# motor_shield_A.net
KiCad netlist of a schematic drawn in EAGLE
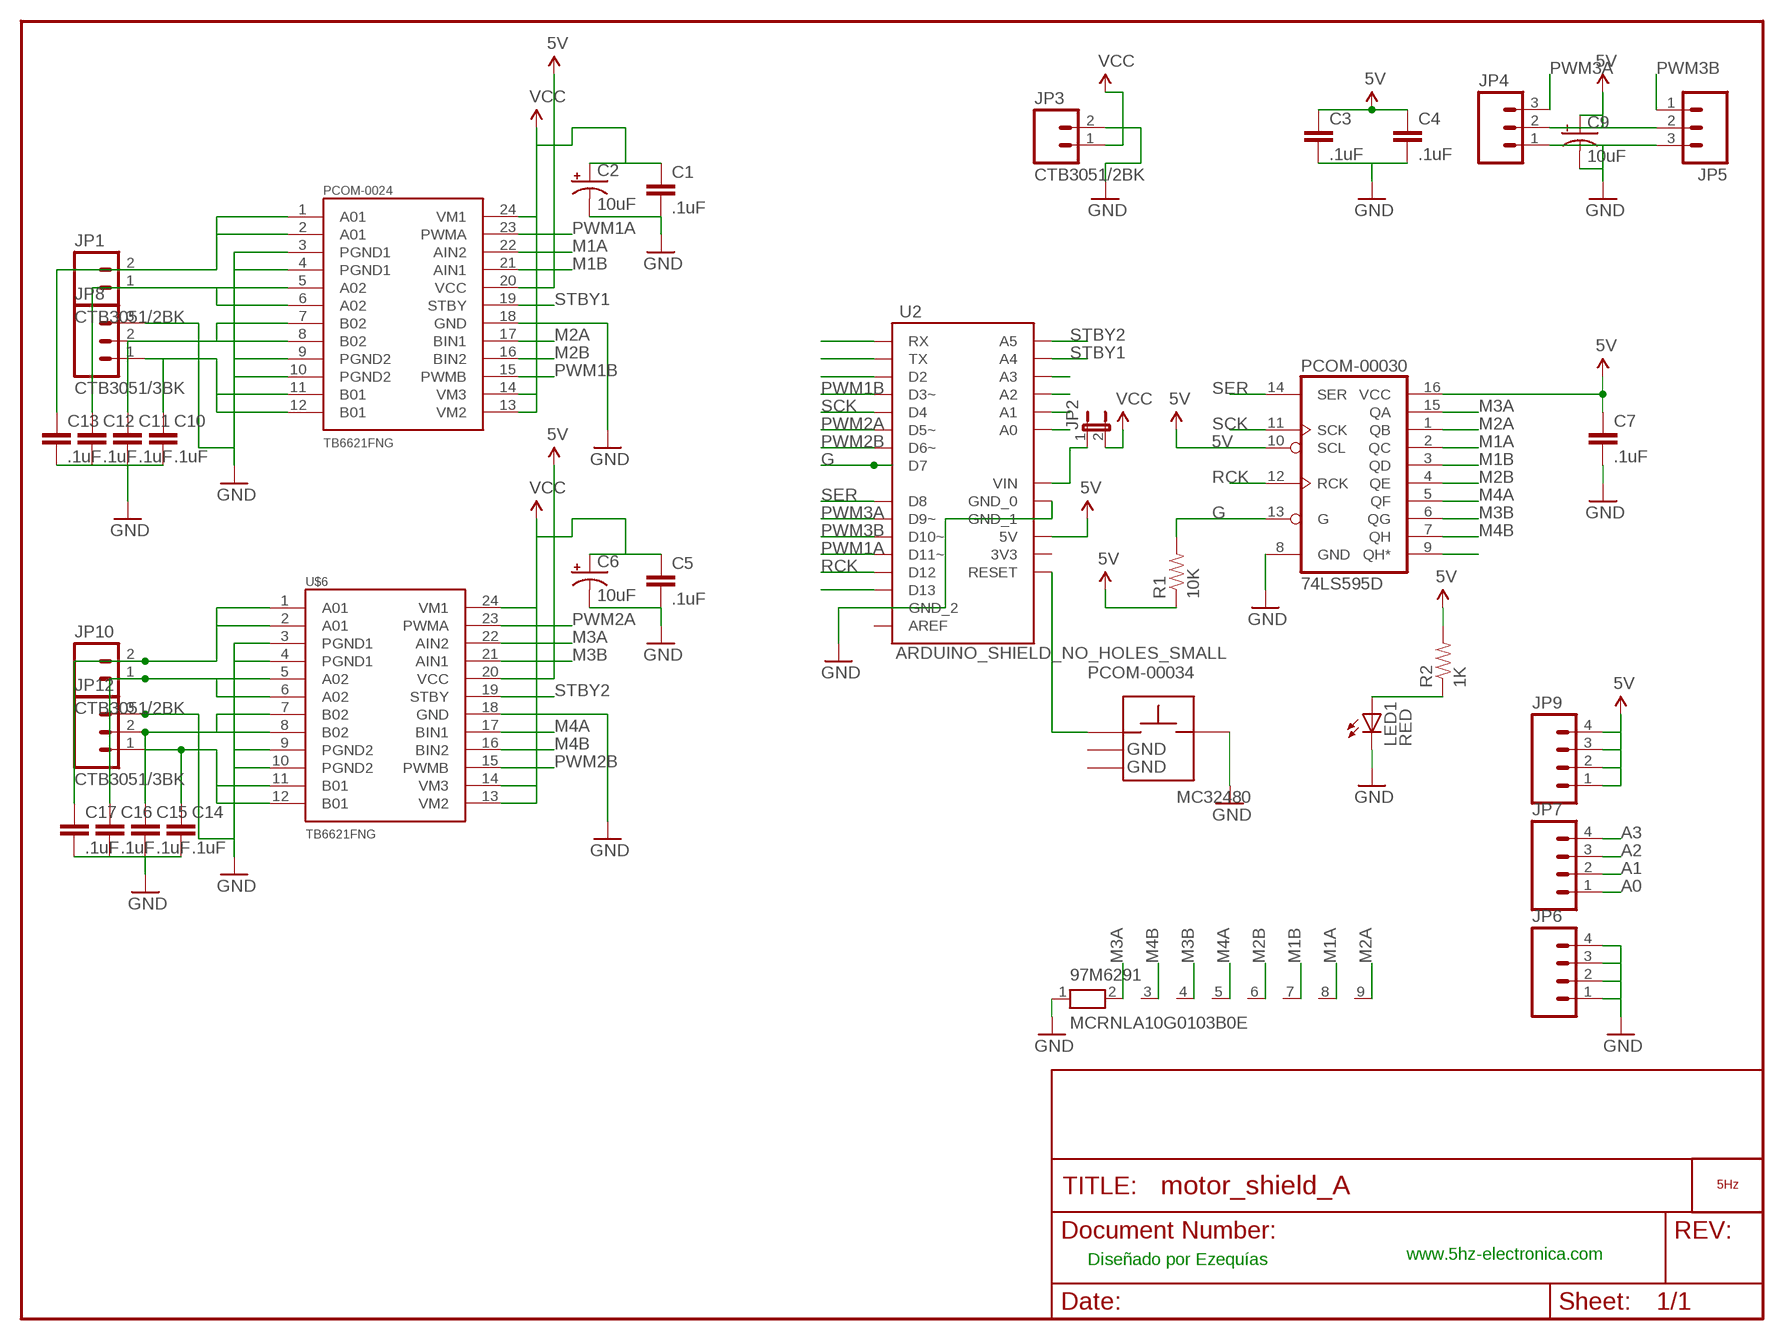
[diagram p0: schematic, sheet 1]

(export (version "E")
  (design (tool "Eeschema 10.0.6"))
  (components
    (comp (ref "97M6291")
      (value "MCRNLA10G0103B0E")
      (footprint "eagle-import:RN-9")
      (libsource (lib "eagle-import") (part "RN08"))
    )
    (comp (ref "C1")
      (value ".1uF")
      (footprint "eagle-import:0603-CAP")
      (libsource (lib "eagle-import") (part "CAP0603-CAP"))
    )
    (comp (ref "C2")
      (value "10uF")
      (footprint "eagle-import:EIA3528-KIT")
      (libsource (lib "eagle-import") (part "CAP_POL3528-KIT"))
    )
    (comp (ref "C3")
      (value ".1uF")
      (footprint "eagle-import:0603-CAP")
      (libsource (lib "eagle-import") (part "CAP0603-CAP"))
    )
    (comp (ref "C4")
      (value ".1uF")
      (footprint "eagle-import:0603-CAP")
      (libsource (lib "eagle-import") (part "CAP0603-CAP"))
    )
    (comp (ref "C5")
      (value ".1uF")
      (footprint "eagle-import:0603-CAP")
      (libsource (lib "eagle-import") (part "CAP0603-CAP"))
    )
    (comp (ref "C6")
      (value "10uF")
      (footprint "eagle-import:EIA3528-KIT")
      (libsource (lib "eagle-import") (part "CAP_POL3528-KIT"))
    )
    (comp (ref "C7")
      (value ".1uF")
      (footprint "eagle-import:0603-CAP")
      (libsource (lib "eagle-import") (part "CAP0603-CAP"))
    )
    (comp (ref "C9")
      (value "10uF")
      (footprint "eagle-import:EIA3216")
      (libsource (lib "eagle-import") (part "CAP_POL1206"))
    )
    (comp (ref "C10")
      (value ".1uF")
      (footprint "eagle-import:0603-CAP")
      (libsource (lib "eagle-import") (part "CAP0603-CAP"))
    )
    (comp (ref "C11")
      (value ".1uF")
      (footprint "eagle-import:0603-CAP")
      (libsource (lib "eagle-import") (part "CAP0603-CAP"))
    )
    (comp (ref "C12")
      (value ".1uF")
      (footprint "eagle-import:0603-CAP")
      (libsource (lib "eagle-import") (part "CAP0603-CAP"))
    )
    (comp (ref "C13")
      (value ".1uF")
      (footprint "eagle-import:0603-CAP")
      (libsource (lib "eagle-import") (part "CAP0603-CAP"))
    )
    (comp (ref "C14")
      (value ".1uF")
      (footprint "eagle-import:0603-CAP")
      (libsource (lib "eagle-import") (part "CAP0603-CAP"))
    )
    (comp (ref "C15")
      (value ".1uF")
      (footprint "eagle-import:0603-CAP")
      (libsource (lib "eagle-import") (part "CAP0603-CAP"))
    )
    (comp (ref "C16")
      (value ".1uF")
      (footprint "eagle-import:0603-CAP")
      (libsource (lib "eagle-import") (part "CAP0603-CAP"))
    )
    (comp (ref "C17")
      (value ".1uF")
      (footprint "eagle-import:0603-CAP")
      (libsource (lib "eagle-import") (part "CAP0603-CAP"))
    )
    (comp (ref "JP1")
      (value "CTB3051/2BK")
      (footprint "eagle-import:SCREWTERMINAL-3.5MM-2")
      (libsource (lib "eagle-import") (part "M023.5MM"))
    )
    (comp (ref "JP2")
      (value "JUMPER-2PTH")
      (footprint "eagle-import:1X02")
      (libsource (lib "eagle-import") (part "JUMPER-2PTH"))
    )
    (comp (ref "JP3")
      (value "CTB3051/2BK")
      (footprint "eagle-import:SCREWTERMINAL-3.5MM-2")
      (libsource (lib "eagle-import") (part "M023.5MM"))
    )
    (comp (ref "JP4")
      (value "M03PTH")
      (footprint "eagle-import:1X03")
      (libsource (lib "eagle-import") (part "SparkFun_old_M03PTH"))
    )
    (comp (ref "JP5")
      (value "M03PTH")
      (footprint "eagle-import:1X03")
      (libsource (lib "eagle-import") (part "SparkFun_old_M03PTH"))
    )
    (comp (ref "JP6")
      (value "M04PTH")
      (footprint "eagle-import:1X04")
      (libsource (lib "eagle-import") (part "M04PTH"))
    )
    (comp (ref "JP7")
      (value "M04PTH")
      (footprint "eagle-import:1X04")
      (libsource (lib "eagle-import") (part "M04PTH"))
    )
    (comp (ref "JP8")
      (value "CTB3051/3BK")
      (footprint "eagle-import:SCREWTERMINAL-3.5MM-3")
      (libsource (lib "eagle-import") (part "M03SCREW"))
    )
    (comp (ref "JP9")
      (value "M04PTH")
      (footprint "eagle-import:1X04")
      (libsource (lib "eagle-import") (part "M04PTH"))
    )
    (comp (ref "JP10")
      (value "CTB3051/2BK")
      (footprint "eagle-import:SCREWTERMINAL-3.5MM-2")
      (libsource (lib "eagle-import") (part "M023.5MM"))
    )
    (comp (ref "JP12")
      (value "CTB3051/3BK")
      (footprint "eagle-import:SCREWTERMINAL-3.5MM-3")
      (libsource (lib "eagle-import") (part "M03SCREW"))
    )
    (comp (ref "LED1")
      (value "RED")
      (footprint "eagle-import:LED-0603")
      (libsource (lib "eagle-import") (part "LED0603"))
    )
    (comp (ref "LOGO1")
      (value "LOGO_5HZ_H_COOPER_10MM")
      (footprint "eagle-import:5HZ_LOGO_H_COOPER_10MM")
      (libsource (lib "eagle-import") (part "LOGO_5HZ_H_COOPER_10MM"))
    )
    (comp (ref "PCOM-0024")
      (value "TB6621FNG")
      (footprint "eagle-import:SSOP24")
      (libsource (lib "eagle-import") (part "TB6621FNG"))
    )
    (comp (ref "PCOM-00030")
      (value "74LS595D")
      (footprint "eagle-import:SO16")
      (libsource (lib "eagle-import") (part "74595DLS"))
    )
    (comp (ref "PCOM-00034")
      (value "MC32480")
      (footprint "eagle-import:MC32840")
      (libsource (lib "eagle-import") (part "TACTILE_SWITCH_MC32480"))
    )
    (comp (ref "R1")
      (value "10K")
      (footprint "eagle-import:0603-RES")
      (libsource (lib "eagle-import") (part "RESISTOR0603-RES"))
    )
    (comp (ref "R2")
      (value "1K")
      (footprint "eagle-import:0603-RES")
      (libsource (lib "eagle-import") (part "RESISTOR0603-RES"))
    )
    (comp (ref "U$6")
      (value "TB6621FNG")
      (footprint "eagle-import:SSOP24")
      (libsource (lib "eagle-import") (part "TB6621FNG"))
    )
    (comp (ref "U2")
      (value "ARDUINO_SHIELD_NO_HOLES_SMALL")
      (footprint "eagle-import:UNO_SHIELD_SMALL_NO_HOLES")
      (libsource (lib "eagle-import") (part "ARDUINO_SHIELD_NO_HOLES_SMALL"))
    )
  )
  (nets
    (net (code "1") (name "/A0") (class "Default")
      (node (ref "JP7") (pin "1") (pinfunction "1_1") (pintype "passive"))
      (node (ref "U2") (pin "A0") (pinfunction "A0_A0") (pintype "bidirectional"))
    )
    (net (code "2") (name "/A1") (class "Default")
      (node (ref "JP7") (pin "2") (pinfunction "2_2") (pintype "passive"))
      (node (ref "U2") (pin "A1") (pinfunction "A1_A1") (pintype "bidirectional"))
    )
    (net (code "3") (name "/A2") (class "Default")
      (node (ref "JP7") (pin "3") (pinfunction "3_3") (pintype "passive"))
      (node (ref "U2") (pin "A2") (pinfunction "A2_A2") (pintype "bidirectional"))
    )
    (net (code "4") (name "/A3") (class "Default")
      (node (ref "JP7") (pin "4") (pinfunction "4_4") (pintype "passive"))
      (node (ref "U2") (pin "A3") (pinfunction "A3_A3") (pintype "bidirectional"))
    )
    (net (code "5") (name "/G") (class "Default")
      (node (ref "PCOM-00030") (pin "13") (pinfunction "G_13") (pintype "input"))
      (node (ref "R1") (pin "2") (pinfunction "2_2") (pintype "passive"))
      (node (ref "U2") (pin "D7") (pinfunction "D7_D7") (pintype "bidirectional"))
    )
    (net (code "6") (name "/M1A") (class "Default")
      (node (ref "97M6291") (pin "8") (pinfunction "8_8") (pintype "passive"))
      (node (ref "PCOM-00030") (pin "2") (pinfunction "QC_2") (pintype "tri_state"))
      (node (ref "PCOM-0024") (pin "22") (pinfunction "AIN2_22") (pintype "bidirectional"))
    )
    (net (code "7") (name "/M1B") (class "Default")
      (node (ref "97M6291") (pin "7") (pinfunction "7_7") (pintype "passive"))
      (node (ref "PCOM-00030") (pin "3") (pinfunction "QD_3") (pintype "tri_state"))
      (node (ref "PCOM-0024") (pin "21") (pinfunction "AIN1_21") (pintype "bidirectional"))
    )
    (net (code "8") (name "/M2A") (class "Default")
      (node (ref "97M6291") (pin "9") (pinfunction "9_9") (pintype "passive"))
      (node (ref "PCOM-00030") (pin "1") (pinfunction "QB_1") (pintype "tri_state"))
      (node (ref "PCOM-0024") (pin "17") (pinfunction "BIN1_17") (pintype "bidirectional"))
    )
    (net (code "9") (name "/M2B") (class "Default")
      (node (ref "97M6291") (pin "6") (pinfunction "6_6") (pintype "passive"))
      (node (ref "PCOM-00030") (pin "4") (pinfunction "QE_4") (pintype "tri_state"))
      (node (ref "PCOM-0024") (pin "16") (pinfunction "BIN2_16") (pintype "bidirectional"))
    )
    (net (code "10") (name "/M3A") (class "Default")
      (node (ref "97M6291") (pin "2") (pinfunction "2_2") (pintype "passive"))
      (node (ref "PCOM-00030") (pin "15") (pinfunction "QA_15") (pintype "tri_state"))
      (node (ref "U$6") (pin "22") (pinfunction "AIN2_22") (pintype "bidirectional"))
    )
    (net (code "11") (name "/M3B") (class "Default")
      (node (ref "97M6291") (pin "4") (pinfunction "4_4") (pintype "passive"))
      (node (ref "PCOM-00030") (pin "6") (pinfunction "QG_6") (pintype "tri_state"))
      (node (ref "U$6") (pin "21") (pinfunction "AIN1_21") (pintype "bidirectional"))
    )
    (net (code "12") (name "/M4A") (class "Default")
      (node (ref "97M6291") (pin "5") (pinfunction "5_5") (pintype "passive"))
      (node (ref "PCOM-00030") (pin "5") (pinfunction "QF_5") (pintype "tri_state"))
      (node (ref "U$6") (pin "17") (pinfunction "BIN1_17") (pintype "bidirectional"))
    )
    (net (code "13") (name "/M4B") (class "Default")
      (node (ref "97M6291") (pin "3") (pinfunction "3_3") (pintype "passive"))
      (node (ref "PCOM-00030") (pin "7") (pinfunction "QH_7") (pintype "tri_state"))
      (node (ref "U$6") (pin "16") (pinfunction "BIN2_16") (pintype "bidirectional"))
    )
    (net (code "14") (name "/PWM1A") (class "Default")
      (node (ref "PCOM-0024") (pin "23") (pinfunction "PWMA_23") (pintype "bidirectional"))
      (node (ref "U2") (pin "D11") (pinfunction "D11~{}_D11") (pintype "bidirectional"))
    )
    (net (code "15") (name "/PWM1B") (class "Default")
      (node (ref "PCOM-0024") (pin "15") (pinfunction "PWMB_15") (pintype "bidirectional"))
      (node (ref "U2") (pin "D3") (pinfunction "D3~{}_D3") (pintype "bidirectional"))
    )
    (net (code "16") (name "/PWM2A") (class "Default")
      (node (ref "U$6") (pin "23") (pinfunction "PWMA_23") (pintype "bidirectional"))
      (node (ref "U2") (pin "D5") (pinfunction "D5~{}_D5") (pintype "bidirectional"))
    )
    (net (code "17") (name "/PWM2B") (class "Default")
      (node (ref "U$6") (pin "15") (pinfunction "PWMB_15") (pintype "bidirectional"))
      (node (ref "U2") (pin "D6") (pinfunction "D6~{}_D6") (pintype "bidirectional"))
    )
    (net (code "18") (name "/PWM3A") (class "Default")
      (node (ref "JP4") (pin "3") (pinfunction "3_3") (pintype "passive"))
      (node (ref "U2") (pin "D9") (pinfunction "D9~{}_D9") (pintype "bidirectional"))
    )
    (net (code "19") (name "/PWM3B") (class "Default")
      (node (ref "JP5") (pin "1") (pinfunction "1_1") (pintype "passive"))
      (node (ref "U2") (pin "D10") (pinfunction "D10~{}_D10") (pintype "bidirectional"))
    )
    (net (code "20") (name "/RCK") (class "Default")
      (node (ref "PCOM-00030") (pin "12") (pinfunction "RCK_12") (pintype "input"))
      (node (ref "U2") (pin "D12") (pinfunction "D12_D12") (pintype "bidirectional"))
    )
    (net (code "21") (name "/SCK") (class "Default")
      (node (ref "PCOM-00030") (pin "11") (pinfunction "SCK_11") (pintype "input"))
      (node (ref "U2") (pin "D4") (pinfunction "D4_D4") (pintype "bidirectional"))
    )
    (net (code "22") (name "/SER") (class "Default")
      (node (ref "PCOM-00030") (pin "14") (pinfunction "SER_14") (pintype "input"))
      (node (ref "U2") (pin "D8") (pinfunction "D8_D8") (pintype "bidirectional"))
    )
    (net (code "23") (name "/STBY1") (class "Default")
      (node (ref "PCOM-0024") (pin "19") (pinfunction "STBY_19") (pintype "bidirectional"))
      (node (ref "U2") (pin "A4") (pinfunction "A4_A4") (pintype "bidirectional"))
    )
    (net (code "24") (name "/STBY2") (class "Default")
      (node (ref "U$6") (pin "19") (pinfunction "STBY_19") (pintype "bidirectional"))
      (node (ref "U2") (pin "A5") (pinfunction "A5_A5") (pintype "bidirectional"))
    )
    (net (code "25") (name "5V") (class "Default")
      (node (ref "C3") (pin "1") (pinfunction "1_1") (pintype "passive"))
      (node (ref "C4") (pin "1") (pinfunction "1_1") (pintype "passive"))
      (node (ref "C7") (pin "1") (pinfunction "1_1") (pintype "passive"))
      (node (ref "C9") (pin "A") (pinfunction "+_A") (pintype "passive"))
      (node (ref "JP4") (pin "2") (pinfunction "2_2") (pintype "passive"))
      (node (ref "JP5") (pin "2") (pinfunction "2_2") (pintype "passive"))
      (node (ref "JP9") (pin "1") (pinfunction "1_1") (pintype "passive"))
      (node (ref "JP9") (pin "2") (pinfunction "2_2") (pintype "passive"))
      (node (ref "JP9") (pin "3") (pinfunction "3_3") (pintype "passive"))
      (node (ref "JP9") (pin "4") (pinfunction "4_4") (pintype "passive"))
      (node (ref "PCOM-00030") (pin "10") (pinfunction "SCL_10") (pintype "input"))
      (node (ref "PCOM-00030") (pin "16") (pinfunction "VCC_16") (pintype "power_in"))
      (node (ref "PCOM-0024") (pin "20") (pinfunction "VCC_20") (pintype "bidirectional"))
      (node (ref "R1") (pin "1") (pinfunction "1_1") (pintype "passive"))
      (node (ref "R2") (pin "2") (pinfunction "2_2") (pintype "passive"))
      (node (ref "U$6") (pin "20") (pinfunction "VCC_20") (pintype "bidirectional"))
      (node (ref "U2") (pin "5V") (pinfunction "5V_5V") (pintype "bidirectional"))
    )
    (net (code "26") (name "GND") (class "Default")
      (node (ref "97M6291") (pin "1") (pinfunction "1_1") (pintype "passive"))
      (node (ref "C1") (pin "2") (pinfunction "2_2") (pintype "passive"))
      (node (ref "C10") (pin "2") (pinfunction "2_2") (pintype "passive"))
      (node (ref "C11") (pin "2") (pinfunction "2_2") (pintype "passive"))
      (node (ref "C12") (pin "2") (pinfunction "2_2") (pintype "passive"))
      (node (ref "C13") (pin "2") (pinfunction "2_2") (pintype "passive"))
      (node (ref "C14") (pin "2") (pinfunction "2_2") (pintype "passive"))
      (node (ref "C15") (pin "2") (pinfunction "2_2") (pintype "passive"))
      (node (ref "C16") (pin "2") (pinfunction "2_2") (pintype "passive"))
      (node (ref "C17") (pin "2") (pinfunction "2_2") (pintype "passive"))
      (node (ref "C2") (pin "C") (pinfunction "-_C") (pintype "passive"))
      (node (ref "C3") (pin "2") (pinfunction "2_2") (pintype "passive"))
      (node (ref "C4") (pin "2") (pinfunction "2_2") (pintype "passive"))
      (node (ref "C5") (pin "2") (pinfunction "2_2") (pintype "passive"))
      (node (ref "C6") (pin "C") (pinfunction "-_C") (pintype "passive"))
      (node (ref "C7") (pin "2") (pinfunction "2_2") (pintype "passive"))
      (node (ref "C9") (pin "C") (pinfunction "-_C") (pintype "passive"))
      (node (ref "JP12") (pin "3") (pinfunction "3_3") (pintype "passive"))
      (node (ref "JP3") (pin "2") (pinfunction "2_2") (pintype "passive"))
      (node (ref "JP4") (pin "1") (pinfunction "1_1") (pintype "passive"))
      (node (ref "JP5") (pin "3") (pinfunction "3_3") (pintype "passive"))
      (node (ref "JP6") (pin "1") (pinfunction "1_1") (pintype "passive"))
      (node (ref "JP6") (pin "2") (pinfunction "2_2") (pintype "passive"))
      (node (ref "JP6") (pin "3") (pinfunction "3_3") (pintype "passive"))
      (node (ref "JP6") (pin "4") (pinfunction "4_4") (pintype "passive"))
      (node (ref "JP8") (pin "3") (pinfunction "3_3") (pintype "passive"))
      (node (ref "LED1") (pin "C") (pinfunction "C_C") (pintype "passive"))
      (node (ref "PCOM-00030") (pin "8") (pinfunction "GND_8") (pintype "power_in"))
      (node (ref "PCOM-00034") (pin "B") (pinfunction "B_B") (pintype "passive"))
      (node (ref "PCOM-0024") (pin "10") (pinfunction "PGND2_10") (pintype "bidirectional"))
      (node (ref "PCOM-0024") (pin "18") (pinfunction "GND_18") (pintype "bidirectional"))
      (node (ref "PCOM-0024") (pin "3") (pinfunction "PGND1_3") (pintype "bidirectional"))
      (node (ref "PCOM-0024") (pin "4") (pinfunction "PGND1_4") (pintype "bidirectional"))
      (node (ref "PCOM-0024") (pin "9") (pinfunction "PGND2_9") (pintype "bidirectional"))
      (node (ref "U$6") (pin "10") (pinfunction "PGND2_10") (pintype "bidirectional"))
      (node (ref "U$6") (pin "18") (pinfunction "GND_18") (pintype "bidirectional"))
      (node (ref "U$6") (pin "3") (pinfunction "PGND1_3") (pintype "bidirectional"))
      (node (ref "U$6") (pin "4") (pinfunction "PGND1_4") (pintype "bidirectional"))
      (node (ref "U$6") (pin "9") (pinfunction "PGND2_9") (pintype "bidirectional"))
      (node (ref "U2") (pin "GND_0") (pinfunction "GND_0_GND_0") (pintype "bidirectional"))
      (node (ref "U2") (pin "GND_1") (pinfunction "GND_1_GND_1") (pintype "bidirectional"))
      (node (ref "U2") (pin "GND_2") (pinfunction "GND_2_GND_2") (pintype "bidirectional"))
    )
    (net (code "27") (name "Net-(C10-Pad1)") (class "Default")
      (node (ref "C10") (pin "1") (pinfunction "1_1") (pintype "passive"))
      (node (ref "JP8") (pin "1") (pinfunction "1_1") (pintype "passive"))
      (node (ref "PCOM-0024") (pin "11") (pinfunction "B01_11") (pintype "bidirectional"))
      (node (ref "PCOM-0024") (pin "12") (pinfunction "B01_12") (pintype "bidirectional"))
    )
    (net (code "28") (name "Net-(C11-Pad1)") (class "Default")
      (node (ref "C11") (pin "1") (pinfunction "1_1") (pintype "passive"))
      (node (ref "JP8") (pin "2") (pinfunction "2_2") (pintype "passive"))
      (node (ref "PCOM-0024") (pin "7") (pinfunction "B02_7") (pintype "bidirectional"))
      (node (ref "PCOM-0024") (pin "8") (pinfunction "B02_8") (pintype "bidirectional"))
    )
    (net (code "29") (name "Net-(C12-Pad1)") (class "Default")
      (node (ref "C12") (pin "1") (pinfunction "1_1") (pintype "passive"))
      (node (ref "JP1") (pin "1") (pinfunction "1_1") (pintype "passive"))
      (node (ref "PCOM-0024") (pin "5") (pinfunction "A02_5") (pintype "bidirectional"))
      (node (ref "PCOM-0024") (pin "6") (pinfunction "A02_6") (pintype "bidirectional"))
    )
    (net (code "30") (name "Net-(C13-Pad1)") (class "Default")
      (node (ref "C13") (pin "1") (pinfunction "1_1") (pintype "passive"))
      (node (ref "JP1") (pin "2") (pinfunction "2_2") (pintype "passive"))
      (node (ref "PCOM-0024") (pin "1") (pinfunction "A01_1") (pintype "bidirectional"))
      (node (ref "PCOM-0024") (pin "2") (pinfunction "A01_2") (pintype "bidirectional"))
    )
    (net (code "31") (name "Net-(C14-Pad1)") (class "Default")
      (node (ref "C14") (pin "1") (pinfunction "1_1") (pintype "passive"))
      (node (ref "JP12") (pin "1") (pinfunction "1_1") (pintype "passive"))
      (node (ref "U$6") (pin "11") (pinfunction "B01_11") (pintype "bidirectional"))
      (node (ref "U$6") (pin "12") (pinfunction "B01_12") (pintype "bidirectional"))
    )
    (net (code "32") (name "Net-(C15-Pad1)") (class "Default")
      (node (ref "C15") (pin "1") (pinfunction "1_1") (pintype "passive"))
      (node (ref "JP12") (pin "2") (pinfunction "2_2") (pintype "passive"))
      (node (ref "U$6") (pin "7") (pinfunction "B02_7") (pintype "bidirectional"))
      (node (ref "U$6") (pin "8") (pinfunction "B02_8") (pintype "bidirectional"))
    )
    (net (code "33") (name "Net-(C16-Pad1)") (class "Default")
      (node (ref "C16") (pin "1") (pinfunction "1_1") (pintype "passive"))
      (node (ref "JP10") (pin "1") (pinfunction "1_1") (pintype "passive"))
      (node (ref "U$6") (pin "5") (pinfunction "A02_5") (pintype "bidirectional"))
      (node (ref "U$6") (pin "6") (pinfunction "A02_6") (pintype "bidirectional"))
    )
    (net (code "34") (name "Net-(C17-Pad1)") (class "Default")
      (node (ref "C17") (pin "1") (pinfunction "1_1") (pintype "passive"))
      (node (ref "JP10") (pin "2") (pinfunction "2_2") (pintype "passive"))
      (node (ref "U$6") (pin "1") (pinfunction "A01_1") (pintype "bidirectional"))
      (node (ref "U$6") (pin "2") (pinfunction "A01_2") (pintype "bidirectional"))
    )
    (net (code "35") (name "Net-(JP2-Pad1)") (class "Default")
      (node (ref "JP2") (pin "1") (pinfunction "1_1") (pintype "passive"))
      (node (ref "U2") (pin "VIN") (pinfunction "VIN_VIN") (pintype "bidirectional"))
    )
    (net (code "36") (name "Net-(LED1-PadA)") (class "Default")
      (node (ref "LED1") (pin "A") (pinfunction "A_A") (pintype "passive"))
      (node (ref "R2") (pin "1") (pinfunction "1_1") (pintype "passive"))
    )
    (net (code "37") (name "Net-(PCOM-00034-A)") (class "Default")
      (node (ref "PCOM-00034") (pin "A@1") (pinfunction "A_A@1") (pintype "passive"))
      (node (ref "U2") (pin "RES") (pinfunction "RESET_RES") (pintype "bidirectional"))
    )
    (net (code "38") (name "VCC") (class "Default")
      (node (ref "C1") (pin "1") (pinfunction "1_1") (pintype "passive"))
      (node (ref "C2") (pin "A") (pinfunction "+_A") (pintype "passive"))
      (node (ref "C5") (pin "1") (pinfunction "1_1") (pintype "passive"))
      (node (ref "C6") (pin "A") (pinfunction "+_A") (pintype "passive"))
      (node (ref "JP2") (pin "2") (pinfunction "2_2") (pintype "passive"))
      (node (ref "JP3") (pin "1") (pinfunction "1_1") (pintype "passive"))
      (node (ref "PCOM-0024") (pin "13") (pinfunction "VM2_13") (pintype "bidirectional"))
      (node (ref "PCOM-0024") (pin "14") (pinfunction "VM3_14") (pintype "bidirectional"))
      (node (ref "PCOM-0024") (pin "24") (pinfunction "VM1_24") (pintype "bidirectional"))
      (node (ref "U$6") (pin "13") (pinfunction "VM2_13") (pintype "bidirectional"))
      (node (ref "U$6") (pin "14") (pinfunction "VM3_14") (pintype "bidirectional"))
      (node (ref "U$6") (pin "24") (pinfunction "VM1_24") (pintype "bidirectional"))
    )
    (net (code "39") (name "unconnected-(PCOM-00030-QH*-Pad9)") (class "Default")
      (node (ref "PCOM-00030") (pin "9") (pinfunction "QH*_9") (pintype "tri_state"))
    )
    (net (code "40") (name "unconnected-(PCOM-00034-GND-PadGND@1)") (class "Default")
      (node (ref "PCOM-00034") (pin "GND@1") (pinfunction "GND_GND@1") (pintype "bidirectional"))
    )
    (net (code "41") (name "unconnected-(PCOM-00034-GND-PadGND@2)") (class "Default")
      (node (ref "PCOM-00034") (pin "GND@2") (pinfunction "GND_GND@2") (pintype "bidirectional"))
    )
    (net (code "42") (name "unconnected-(U2-3V3-Pad3.3V)") (class "Default")
      (node (ref "U2") (pin "3.3V") (pinfunction "3V3_3.3V") (pintype "bidirectional"))
    )
    (net (code "43") (name "unconnected-(U2-PadAREF)") (class "Default")
      (node (ref "U2") (pin "AREF") (pinfunction "AREF_AREF") (pintype "bidirectional"))
    )
    (net (code "44") (name "unconnected-(U2-PadD2)") (class "Default")
      (node (ref "U2") (pin "D2") (pinfunction "D2_D2") (pintype "bidirectional"))
    )
    (net (code "45") (name "unconnected-(U2-PadD13)") (class "Default")
      (node (ref "U2") (pin "D13") (pinfunction "D13_D13") (pintype "bidirectional"))
    )
    (net (code "46") (name "unconnected-(U2-PadRX)") (class "Default")
      (node (ref "U2") (pin "RX") (pinfunction "RX_RX") (pintype "bidirectional"))
    )
    (net (code "47") (name "unconnected-(U2-PadTX)") (class "Default")
      (node (ref "U2") (pin "TX") (pinfunction "TX_TX") (pintype "bidirectional"))
    )
  )
)
